# pulsewidth2.net
KiCad netlist of a schematic drawn in Altium Designer
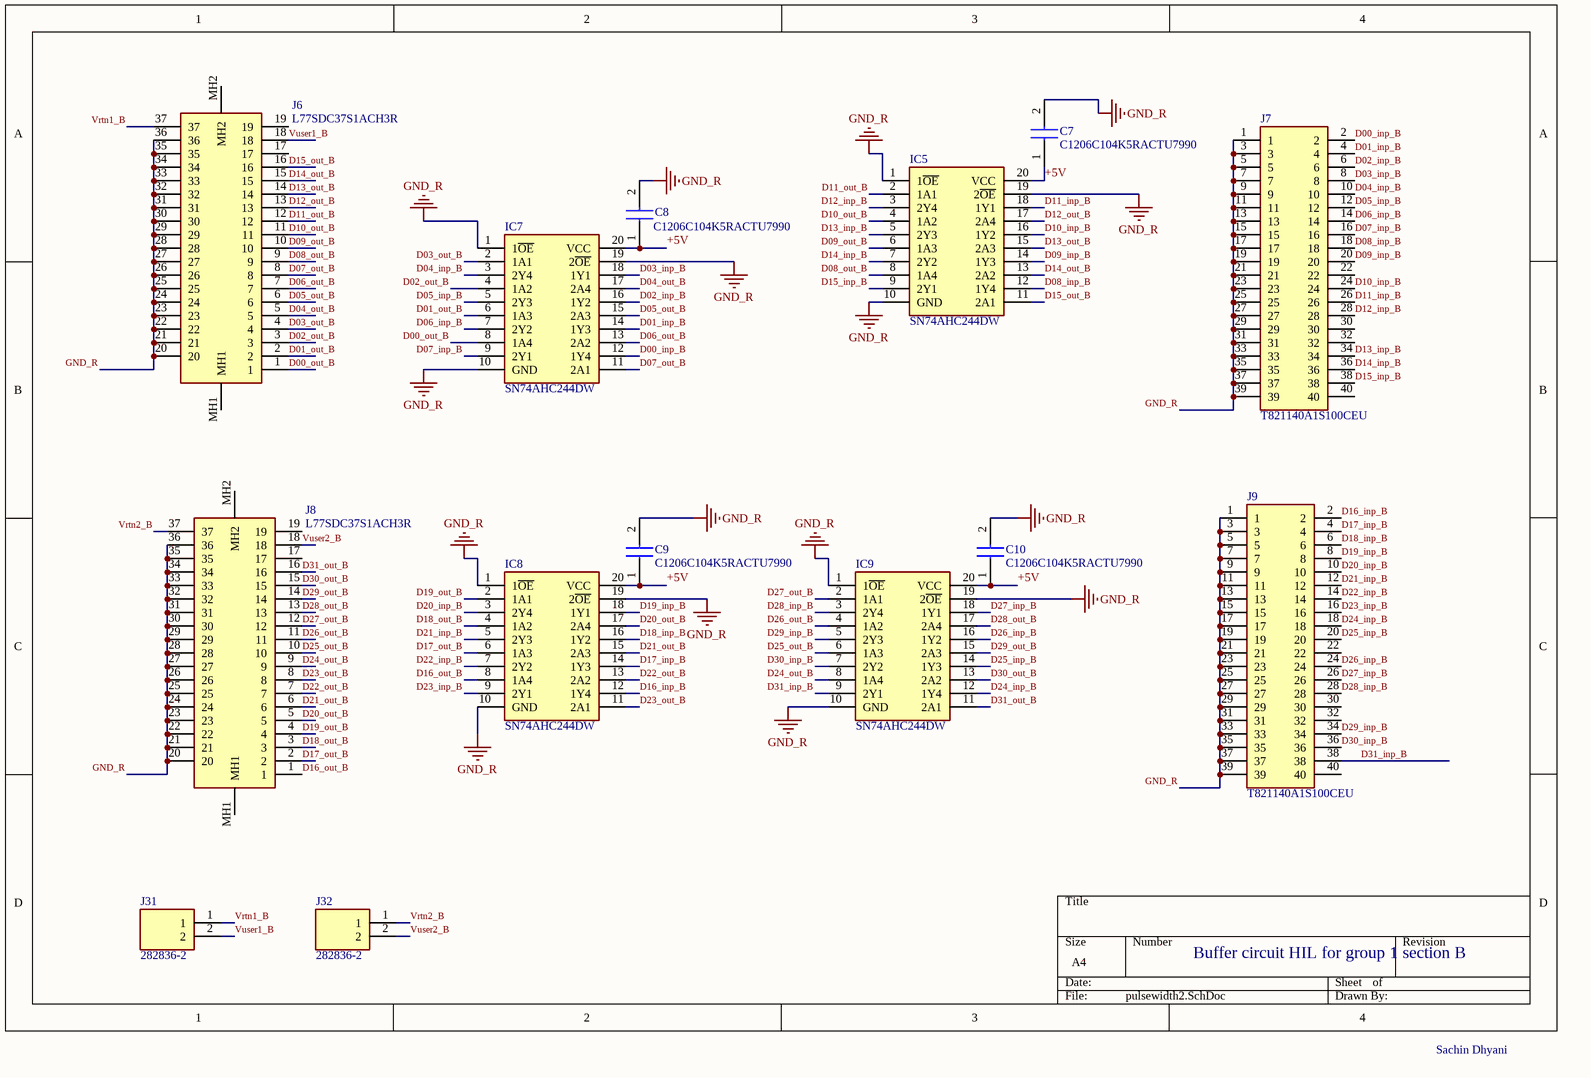
[diagram p0: pulsewidth2.SchDoc]

(export (version "E")
  (design (tool "Eeschema 10.0.6"))
  (components
    (comp (ref "C7")
      (value "C1206C104K5RACTU7990")
      (footprint "SamacSys:CAPC3216X88N")
      (description "Capacitor")
      (libsource (lib "*") (part "C1206C104K5RACTU7990"))
    )
    (comp (ref "C8")
      (value "C1206C104K5RACTU7990")
      (footprint "SamacSys:CAPC3216X88N")
      (description "Capacitor")
      (libsource (lib "*") (part "C1206C104K5RACTU7990"))
    )
    (comp (ref "C9")
      (value "C1206C104K5RACTU7990")
      (footprint "SamacSys:CAPC3216X88N")
      (description "Capacitor")
      (libsource (lib "*") (part "C1206C104K5RACTU7990"))
    )
    (comp (ref "C10")
      (value "C1206C104K5RACTU7990")
      (footprint "SamacSys:CAPC3216X88N")
      (description "Capacitor")
      (libsource (lib "*") (part "C1206C104K5RACTU7990"))
    )
    (comp (ref "IC5")
      (value "SN74AHC244DW")
      (footprint "SamacSys:SOIC127P1030X265-20N")
      (description "Integrated Circuit")
      (fields (field (name "MOUSER PART NUMBER") "595-SN74AHC244DW"))
      (libsource (lib "*") (part "SN74AHC244DW"))
    )
    (comp (ref "IC7")
      (value "SN74AHC244DW")
      (footprint "SamacSys:SOIC127P1030X265-20N")
      (description "Integrated Circuit")
      (fields (field (name "MOUSER PART NUMBER") "595-SN74AHC244DW"))
      (libsource (lib "*") (part "SN74AHC244DW"))
    )
    (comp (ref "IC8")
      (value "SN74AHC244DW")
      (footprint "SamacSys:SOIC127P1030X265-20N")
      (description "Integrated Circuit")
      (fields (field (name "MOUSER PART NUMBER") "595-SN74AHC244DW"))
      (libsource (lib "*") (part "SN74AHC244DW"))
    )
    (comp (ref "IC9")
      (value "SN74AHC244DW")
      (footprint "SamacSys:SOIC127P1030X265-20N")
      (description "Integrated Circuit")
      (fields (field (name "MOUSER PART NUMBER") "595-SN74AHC244DW"))
      (libsource (lib "*") (part "SN74AHC244DW"))
    )
    (comp (ref "J6")
      (value "L77SDC37S1ACH3R")
      (footprint "L77SDC37S1ACH3R")
      (description "Connector")
      (fields (field (name "MOUSER PART NUMBER") "523-L77SDC37S1ACH3R"))
      (libsource (lib "opel_Rt_comps") (part "L77SDC37S1ACH3R"))
    )
    (comp (ref "J7")
      (value "T821140A1S100CEU")
      (footprint "SamacSys:SHDR40W64P254X254_2X20_5842X895X915P")
      (description "Connector")
      (libsource (lib "*") (part "T821140A1S100CEU"))
    )
    (comp (ref "J8")
      (value "L77SDC37S1ACH3R")
      (footprint "L77SDC37S1ACH3R")
      (description "Connector")
      (fields (field (name "MOUSER PART NUMBER") "523-L77SDC37S1ACH3R"))
      (libsource (lib "opel_Rt_comps") (part "L77SDC37S1ACH3R"))
    )
    (comp (ref "J9")
      (value "T821140A1S100CEU")
      (footprint "SamacSys:SHDR40W64P254X254_2X20_5842X895X915P")
      (description "Connector")
      (libsource (lib "*") (part "T821140A1S100CEU"))
    )
    (comp (ref "J31")
      (value "282836-2")
      (footprint "SamacSys:2828362")
      (description "Connector")
      (fields (field (name "MOUSER PART NUMBER") "571-2828362"))
      (libsource (lib "*") (part "282836-2"))
    )
    (comp (ref "J32")
      (value "282836-2")
      (footprint "SamacSys:2828362")
      (description "Connector")
      (fields (field (name "MOUSER PART NUMBER") "571-2828362"))
      (libsource (lib "*") (part "282836-2"))
    )
  )
  (nets
    (net (code "1") (name "/+5V") (class "Default")
      (node (ref "C10") (pin "1") (pinfunction "1_1") (pintype "passive"))
      (node (ref "C7") (pin "1") (pinfunction "1_1") (pintype "passive"))
      (node (ref "C8") (pin "1") (pinfunction "1_1") (pintype "passive"))
      (node (ref "C9") (pin "1") (pinfunction "1_1") (pintype "passive"))
      (node (ref "IC5") (pin "20") (pinfunction "VCC_20") (pintype "passive"))
      (node (ref "IC7") (pin "20") (pinfunction "VCC_20") (pintype "passive"))
      (node (ref "IC8") (pin "20") (pinfunction "VCC_20") (pintype "passive"))
      (node (ref "IC9") (pin "20") (pinfunction "VCC_20") (pintype "passive"))
    )
    (net (code "2") (name "/D00_inp_B") (class "Default")
      (node (ref "IC7") (pin "12") (pinfunction "1Y4_12") (pintype "passive"))
      (node (ref "J7") (pin "2") (pinfunction "2_2") (pintype "passive"))
    )
    (net (code "3") (name "/D00_out_B") (class "Default")
      (node (ref "IC7") (pin "8") (pinfunction "1A4_8") (pintype "passive"))
      (node (ref "J6") (pin "1") (pinfunction "1_1") (pintype "passive"))
    )
    (net (code "4") (name "/D01_inp_B") (class "Default")
      (node (ref "IC7") (pin "14") (pinfunction "1Y3_14") (pintype "passive"))
      (node (ref "J7") (pin "4") (pinfunction "4_4") (pintype "passive"))
    )
    (net (code "5") (name "/D01_out_B") (class "Default")
      (node (ref "IC7") (pin "6") (pinfunction "1A3_6") (pintype "passive"))
      (node (ref "J6") (pin "2") (pinfunction "2_2") (pintype "passive"))
    )
    (net (code "6") (name "/D02_inp_B") (class "Default")
      (node (ref "IC7") (pin "16") (pinfunction "1Y2_16") (pintype "passive"))
      (node (ref "J7") (pin "6") (pinfunction "6_6") (pintype "passive"))
    )
    (net (code "7") (name "/D02_out_B") (class "Default")
      (node (ref "IC7") (pin "4") (pinfunction "1A2_4") (pintype "passive"))
      (node (ref "J6") (pin "3") (pinfunction "3_3") (pintype "passive"))
    )
    (net (code "8") (name "/D03_inp_B") (class "Default")
      (node (ref "IC7") (pin "18") (pinfunction "1Y1_18") (pintype "passive"))
      (node (ref "J7") (pin "8") (pinfunction "8_8") (pintype "passive"))
    )
    (net (code "9") (name "/D03_out_B") (class "Default")
      (node (ref "IC7") (pin "2") (pinfunction "1A1_2") (pintype "passive"))
      (node (ref "J6") (pin "4") (pinfunction "4_4") (pintype "passive"))
    )
    (net (code "10") (name "/D04_inp_B") (class "Default")
      (node (ref "IC7") (pin "3") (pinfunction "2Y4_3") (pintype "passive"))
      (node (ref "J7") (pin "10") (pinfunction "10_10") (pintype "passive"))
    )
    (net (code "11") (name "/D04_out_B") (class "Default")
      (node (ref "IC7") (pin "17") (pinfunction "2A4_17") (pintype "passive"))
      (node (ref "J6") (pin "5") (pinfunction "5_5") (pintype "passive"))
    )
    (net (code "12") (name "/D05_inp_B") (class "Default")
      (node (ref "IC7") (pin "5") (pinfunction "2Y3_5") (pintype "passive"))
      (node (ref "J7") (pin "12") (pinfunction "12_12") (pintype "passive"))
    )
    (net (code "13") (name "/D05_out_B") (class "Default")
      (node (ref "IC7") (pin "15") (pinfunction "2A3_15") (pintype "passive"))
      (node (ref "J6") (pin "6") (pinfunction "6_6") (pintype "passive"))
    )
    (net (code "14") (name "/D06_inp_B") (class "Default")
      (node (ref "IC7") (pin "7") (pinfunction "2Y2_7") (pintype "passive"))
      (node (ref "J7") (pin "14") (pinfunction "14_14") (pintype "passive"))
    )
    (net (code "15") (name "/D06_out_B") (class "Default")
      (node (ref "IC7") (pin "13") (pinfunction "2A2_13") (pintype "passive"))
      (node (ref "J6") (pin "7") (pinfunction "7_7") (pintype "passive"))
    )
    (net (code "16") (name "/D07_inp_B") (class "Default")
      (node (ref "IC7") (pin "9") (pinfunction "2Y1_9") (pintype "passive"))
      (node (ref "J7") (pin "16") (pinfunction "16_16") (pintype "passive"))
    )
    (net (code "17") (name "/D07_out_B") (class "Default")
      (node (ref "IC7") (pin "11") (pinfunction "2A1_11") (pintype "passive"))
      (node (ref "J6") (pin "8") (pinfunction "8_8") (pintype "passive"))
    )
    (net (code "18") (name "/D08_inp_B") (class "Default")
      (node (ref "IC5") (pin "12") (pinfunction "1Y4_12") (pintype "passive"))
      (node (ref "J7") (pin "18") (pinfunction "18_18") (pintype "passive"))
    )
    (net (code "19") (name "/D08_out_B") (class "Default")
      (node (ref "IC5") (pin "8") (pinfunction "1A4_8") (pintype "passive"))
      (node (ref "J6") (pin "9") (pinfunction "9_9") (pintype "passive"))
    )
    (net (code "20") (name "/D09_inp_B") (class "Default")
      (node (ref "IC5") (pin "14") (pinfunction "1Y3_14") (pintype "passive"))
      (node (ref "J7") (pin "20") (pinfunction "20_20") (pintype "passive"))
    )
    (net (code "21") (name "/D09_out_B") (class "Default")
      (node (ref "IC5") (pin "6") (pinfunction "1A3_6") (pintype "passive"))
      (node (ref "J6") (pin "10") (pinfunction "10_10") (pintype "passive"))
    )
    (net (code "22") (name "/D10_inp_B") (class "Default")
      (node (ref "IC5") (pin "16") (pinfunction "1Y2_16") (pintype "passive"))
      (node (ref "J7") (pin "24") (pinfunction "24_24") (pintype "passive"))
    )
    (net (code "23") (name "/D10_out_B") (class "Default")
      (node (ref "IC5") (pin "4") (pinfunction "1A2_4") (pintype "passive"))
      (node (ref "J6") (pin "11") (pinfunction "11_11") (pintype "passive"))
    )
    (net (code "24") (name "/D11_inp_B") (class "Default")
      (node (ref "IC5") (pin "18") (pinfunction "1Y1_18") (pintype "passive"))
      (node (ref "J7") (pin "26") (pinfunction "26_26") (pintype "passive"))
    )
    (net (code "25") (name "/D11_out_B") (class "Default")
      (node (ref "IC5") (pin "2") (pinfunction "1A1_2") (pintype "passive"))
      (node (ref "J6") (pin "12") (pinfunction "12_12") (pintype "passive"))
    )
    (net (code "26") (name "/D12_inp_B") (class "Default")
      (node (ref "IC5") (pin "3") (pinfunction "2Y4_3") (pintype "passive"))
      (node (ref "J7") (pin "28") (pinfunction "28_28") (pintype "passive"))
    )
    (net (code "27") (name "/D12_out_B") (class "Default")
      (node (ref "IC5") (pin "17") (pinfunction "2A4_17") (pintype "passive"))
      (node (ref "J6") (pin "13") (pinfunction "13_13") (pintype "passive"))
    )
    (net (code "28") (name "/D13_inp_B") (class "Default")
      (node (ref "IC5") (pin "5") (pinfunction "2Y3_5") (pintype "passive"))
      (node (ref "J7") (pin "34") (pinfunction "34_34") (pintype "passive"))
    )
    (net (code "29") (name "/D13_out_B") (class "Default")
      (node (ref "IC5") (pin "15") (pinfunction "2A3_15") (pintype "passive"))
      (node (ref "J6") (pin "14") (pinfunction "14_14") (pintype "passive"))
    )
    (net (code "30") (name "/D14_inp_B") (class "Default")
      (node (ref "IC5") (pin "7") (pinfunction "2Y2_7") (pintype "passive"))
      (node (ref "J7") (pin "36") (pinfunction "36_36") (pintype "passive"))
    )
    (net (code "31") (name "/D14_out_B") (class "Default")
      (node (ref "IC5") (pin "13") (pinfunction "2A2_13") (pintype "passive"))
      (node (ref "J6") (pin "15") (pinfunction "15_15") (pintype "passive"))
    )
    (net (code "32") (name "/D15_inp_B") (class "Default")
      (node (ref "IC5") (pin "9") (pinfunction "2Y1_9") (pintype "passive"))
      (node (ref "J7") (pin "38") (pinfunction "38_38") (pintype "passive"))
    )
    (net (code "33") (name "/D15_out_B") (class "Default")
      (node (ref "IC5") (pin "11") (pinfunction "2A1_11") (pintype "passive"))
      (node (ref "J6") (pin "16") (pinfunction "16_16") (pintype "passive"))
    )
    (net (code "34") (name "/D16_inp_B") (class "Default")
      (node (ref "IC8") (pin "12") (pinfunction "1Y4_12") (pintype "passive"))
      (node (ref "J9") (pin "2") (pinfunction "2_2") (pintype "passive"))
    )
    (net (code "35") (name "/D16_out_B") (class "Default")
      (node (ref "IC8") (pin "8") (pinfunction "1A4_8") (pintype "passive"))
      (node (ref "J8") (pin "1") (pinfunction "1_1") (pintype "passive"))
    )
    (net (code "36") (name "/D17_inp_B") (class "Default")
      (node (ref "IC8") (pin "14") (pinfunction "1Y3_14") (pintype "passive"))
      (node (ref "J9") (pin "4") (pinfunction "4_4") (pintype "passive"))
    )
    (net (code "37") (name "/D17_out_B") (class "Default")
      (node (ref "IC8") (pin "6") (pinfunction "1A3_6") (pintype "passive"))
      (node (ref "J8") (pin "2") (pinfunction "2_2") (pintype "passive"))
    )
    (net (code "38") (name "/D18_inp_B") (class "Default")
      (node (ref "IC8") (pin "16") (pinfunction "1Y2_16") (pintype "passive"))
      (node (ref "J9") (pin "6") (pinfunction "6_6") (pintype "passive"))
    )
    (net (code "39") (name "/D18_out_B") (class "Default")
      (node (ref "IC8") (pin "4") (pinfunction "1A2_4") (pintype "passive"))
      (node (ref "J8") (pin "3") (pinfunction "3_3") (pintype "passive"))
    )
    (net (code "40") (name "/D19_inp_B") (class "Default")
      (node (ref "IC8") (pin "18") (pinfunction "1Y1_18") (pintype "passive"))
      (node (ref "J9") (pin "8") (pinfunction "8_8") (pintype "passive"))
    )
    (net (code "41") (name "/D19_out_B") (class "Default")
      (node (ref "IC8") (pin "2") (pinfunction "1A1_2") (pintype "passive"))
      (node (ref "J8") (pin "4") (pinfunction "4_4") (pintype "passive"))
    )
    (net (code "42") (name "/D20_inp_B") (class "Default")
      (node (ref "IC8") (pin "3") (pinfunction "2Y4_3") (pintype "passive"))
      (node (ref "J9") (pin "10") (pinfunction "10_10") (pintype "passive"))
    )
    (net (code "43") (name "/D20_out_B") (class "Default")
      (node (ref "IC8") (pin "17") (pinfunction "2A4_17") (pintype "passive"))
      (node (ref "J8") (pin "5") (pinfunction "5_5") (pintype "passive"))
    )
    (net (code "44") (name "/D21_inp_B") (class "Default")
      (node (ref "IC8") (pin "5") (pinfunction "2Y3_5") (pintype "passive"))
      (node (ref "J9") (pin "12") (pinfunction "12_12") (pintype "passive"))
    )
    (net (code "45") (name "/D21_out_B") (class "Default")
      (node (ref "IC8") (pin "15") (pinfunction "2A3_15") (pintype "passive"))
      (node (ref "J8") (pin "6") (pinfunction "6_6") (pintype "passive"))
    )
    (net (code "46") (name "/D22_inp_B") (class "Default")
      (node (ref "IC8") (pin "7") (pinfunction "2Y2_7") (pintype "passive"))
      (node (ref "J9") (pin "14") (pinfunction "14_14") (pintype "passive"))
    )
    (net (code "47") (name "/D22_out_B") (class "Default")
      (node (ref "IC8") (pin "13") (pinfunction "2A2_13") (pintype "passive"))
      (node (ref "J8") (pin "7") (pinfunction "7_7") (pintype "passive"))
    )
    (net (code "48") (name "/D23_inp_B") (class "Default")
      (node (ref "IC8") (pin "9") (pinfunction "2Y1_9") (pintype "passive"))
      (node (ref "J9") (pin "16") (pinfunction "16_16") (pintype "passive"))
    )
    (net (code "49") (name "/D23_out_B") (class "Default")
      (node (ref "IC8") (pin "11") (pinfunction "2A1_11") (pintype "passive"))
      (node (ref "J8") (pin "8") (pinfunction "8_8") (pintype "passive"))
    )
    (net (code "50") (name "/D24_inp_B") (class "Default")
      (node (ref "IC9") (pin "12") (pinfunction "1Y4_12") (pintype "passive"))
      (node (ref "J9") (pin "18") (pinfunction "18_18") (pintype "passive"))
    )
    (net (code "51") (name "/D24_out_B") (class "Default")
      (node (ref "IC9") (pin "8") (pinfunction "1A4_8") (pintype "passive"))
      (node (ref "J8") (pin "9") (pinfunction "9_9") (pintype "passive"))
    )
    (net (code "52") (name "/D25_inp_B") (class "Default")
      (node (ref "IC9") (pin "14") (pinfunction "1Y3_14") (pintype "passive"))
      (node (ref "J9") (pin "20") (pinfunction "20_20") (pintype "passive"))
    )
    (net (code "53") (name "/D25_out_B") (class "Default")
      (node (ref "IC9") (pin "6") (pinfunction "1A3_6") (pintype "passive"))
      (node (ref "J8") (pin "10") (pinfunction "10_10") (pintype "passive"))
    )
    (net (code "54") (name "/D26_inp_B") (class "Default")
      (node (ref "IC9") (pin "16") (pinfunction "1Y2_16") (pintype "passive"))
      (node (ref "J9") (pin "24") (pinfunction "24_24") (pintype "passive"))
    )
    (net (code "55") (name "/D26_out_B") (class "Default")
      (node (ref "IC9") (pin "4") (pinfunction "1A2_4") (pintype "passive"))
      (node (ref "J8") (pin "11") (pinfunction "11_11") (pintype "passive"))
    )
    (net (code "56") (name "/D27_inp_B") (class "Default")
      (node (ref "IC9") (pin "18") (pinfunction "1Y1_18") (pintype "passive"))
      (node (ref "J9") (pin "26") (pinfunction "26_26") (pintype "passive"))
    )
    (net (code "57") (name "/D27_out_B") (class "Default")
      (node (ref "IC9") (pin "2") (pinfunction "1A1_2") (pintype "passive"))
      (node (ref "J8") (pin "12") (pinfunction "12_12") (pintype "passive"))
    )
    (net (code "58") (name "/D28_inp_B") (class "Default")
      (node (ref "IC9") (pin "3") (pinfunction "2Y4_3") (pintype "passive"))
      (node (ref "J9") (pin "28") (pinfunction "28_28") (pintype "passive"))
    )
    (net (code "59") (name "/D28_out_B") (class "Default")
      (node (ref "IC9") (pin "17") (pinfunction "2A4_17") (pintype "passive"))
      (node (ref "J8") (pin "13") (pinfunction "13_13") (pintype "passive"))
    )
    (net (code "60") (name "/D29_inp_B") (class "Default")
      (node (ref "IC9") (pin "5") (pinfunction "2Y3_5") (pintype "passive"))
      (node (ref "J9") (pin "34") (pinfunction "34_34") (pintype "passive"))
    )
    (net (code "61") (name "/D29_out_B") (class "Default")
      (node (ref "IC9") (pin "15") (pinfunction "2A3_15") (pintype "passive"))
      (node (ref "J8") (pin "14") (pinfunction "14_14") (pintype "passive"))
    )
    (net (code "62") (name "/D30_inp_B") (class "Default")
      (node (ref "IC9") (pin "7") (pinfunction "2Y2_7") (pintype "passive"))
      (node (ref "J9") (pin "36") (pinfunction "36_36") (pintype "passive"))
    )
    (net (code "63") (name "/D30_out_B") (class "Default")
      (node (ref "IC9") (pin "13") (pinfunction "2A2_13") (pintype "passive"))
      (node (ref "J8") (pin "15") (pinfunction "15_15") (pintype "passive"))
    )
    (net (code "64") (name "/D31_inp_B") (class "Default")
      (node (ref "IC9") (pin "9") (pinfunction "2Y1_9") (pintype "passive"))
      (node (ref "J9") (pin "38") (pinfunction "38_38") (pintype "passive"))
    )
    (net (code "65") (name "/D31_out_B") (class "Default")
      (node (ref "IC9") (pin "11") (pinfunction "2A1_11") (pintype "passive"))
      (node (ref "J8") (pin "16") (pinfunction "16_16") (pintype "passive"))
    )
    (net (code "66") (name "/Vrtn1_B") (class "Default")
      (node (ref "J31") (pin "1") (pinfunction "1_1") (pintype "passive"))
      (node (ref "J6") (pin "37") (pinfunction "37_37") (pintype "passive"))
    )
    (net (code "67") (name "/Vrtn2_B") (class "Default")
      (node (ref "J32") (pin "1") (pinfunction "1_1") (pintype "passive"))
      (node (ref "J8") (pin "37") (pinfunction "37_37") (pintype "passive"))
    )
    (net (code "68") (name "/Vuser1_B") (class "Default")
      (node (ref "J31") (pin "2") (pinfunction "2_2") (pintype "passive"))
      (node (ref "J6") (pin "18") (pinfunction "18_18") (pintype "passive"))
    )
    (net (code "69") (name "/Vuser2_B") (class "Default")
      (node (ref "J32") (pin "2") (pinfunction "2_2") (pintype "passive"))
      (node (ref "J8") (pin "18") (pinfunction "18_18") (pintype "passive"))
    )
    (net (code "70") (name "GND_R") (class "Default")
      (node (ref "C10") (pin "2") (pinfunction "2_2") (pintype "passive"))
      (node (ref "C7") (pin "2") (pinfunction "2_2") (pintype "passive"))
      (node (ref "C8") (pin "2") (pinfunction "2_2") (pintype "passive"))
      (node (ref "C9") (pin "2") (pinfunction "2_2") (pintype "passive"))
      (node (ref "IC5") (pin "1") (pinfunction "1~{OE}_1") (pintype "passive"))
      (node (ref "IC5") (pin "10") (pinfunction "GND_10") (pintype "passive"))
      (node (ref "IC5") (pin "19") (pinfunction "2~{OE}_19") (pintype "passive"))
      (node (ref "IC7") (pin "1") (pinfunction "1~{OE}_1") (pintype "passive"))
      (node (ref "IC7") (pin "10") (pinfunction "GND_10") (pintype "passive"))
      (node (ref "IC7") (pin "19") (pinfunction "2~{OE}_19") (pintype "passive"))
      (node (ref "IC8") (pin "1") (pinfunction "1~{OE}_1") (pintype "passive"))
      (node (ref "IC8") (pin "10") (pinfunction "GND_10") (pintype "passive"))
      (node (ref "IC8") (pin "19") (pinfunction "2~{OE}_19") (pintype "passive"))
      (node (ref "IC9") (pin "1") (pinfunction "1~{OE}_1") (pintype "passive"))
      (node (ref "IC9") (pin "10") (pinfunction "GND_10") (pintype "passive"))
      (node (ref "IC9") (pin "19") (pinfunction "2~{OE}_19") (pintype "passive"))
      (node (ref "J6") (pin "20") (pinfunction "20_20") (pintype "passive"))
      (node (ref "J6") (pin "21") (pinfunction "21_21") (pintype "passive"))
      (node (ref "J6") (pin "22") (pinfunction "22_22") (pintype "passive"))
      (node (ref "J6") (pin "23") (pinfunction "23_23") (pintype "passive"))
      (node (ref "J6") (pin "24") (pinfunction "24_24") (pintype "passive"))
      (node (ref "J6") (pin "25") (pinfunction "25_25") (pintype "passive"))
      (node (ref "J6") (pin "26") (pinfunction "26_26") (pintype "passive"))
      (node (ref "J6") (pin "27") (pinfunction "27_27") (pintype "passive"))
      (node (ref "J6") (pin "28") (pinfunction "28_28") (pintype "passive"))
      (node (ref "J6") (pin "29") (pinfunction "29_29") (pintype "passive"))
      (node (ref "J6") (pin "30") (pinfunction "30_30") (pintype "passive"))
      (node (ref "J6") (pin "31") (pinfunction "31_31") (pintype "passive"))
      (node (ref "J6") (pin "32") (pinfunction "32_32") (pintype "passive"))
      (node (ref "J6") (pin "33") (pinfunction "33_33") (pintype "passive"))
      (node (ref "J6") (pin "34") (pinfunction "34_34") (pintype "passive"))
      (node (ref "J6") (pin "35") (pinfunction "35_35") (pintype "passive"))
      (node (ref "J6") (pin "36") (pinfunction "36_36") (pintype "passive"))
      (node (ref "J7") (pin "1") (pinfunction "1_1") (pintype "passive"))
      (node (ref "J7") (pin "11") (pinfunction "11_11") (pintype "passive"))
      (node (ref "J7") (pin "13") (pinfunction "13_13") (pintype "passive"))
      (node (ref "J7") (pin "15") (pinfunction "15_15") (pintype "passive"))
      (node (ref "J7") (pin "17") (pinfunction "17_17") (pintype "passive"))
      (node (ref "J7") (pin "19") (pinfunction "19_19") (pintype "passive"))
      (node (ref "J7") (pin "21") (pinfunction "21_21") (pintype "passive"))
      (node (ref "J7") (pin "23") (pinfunction "23_23") (pintype "passive"))
      (node (ref "J7") (pin "25") (pinfunction "25_25") (pintype "passive"))
      (node (ref "J7") (pin "27") (pinfunction "27_27") (pintype "passive"))
      (node (ref "J7") (pin "29") (pinfunction "29_29") (pintype "passive"))
      (node (ref "J7") (pin "3") (pinfunction "3_3") (pintype "passive"))
      (node (ref "J7") (pin "31") (pinfunction "31_31") (pintype "passive"))
      (node (ref "J7") (pin "33") (pinfunction "33_33") (pintype "passive"))
      (node (ref "J7") (pin "35") (pinfunction "35_35") (pintype "passive"))
      (node (ref "J7") (pin "37") (pinfunction "37_37") (pintype "passive"))
      (node (ref "J7") (pin "39") (pinfunction "39_39") (pintype "passive"))
      (node (ref "J7") (pin "5") (pinfunction "5_5") (pintype "passive"))
      (node (ref "J7") (pin "7") (pinfunction "7_7") (pintype "passive"))
      (node (ref "J7") (pin "9") (pinfunction "9_9") (pintype "passive"))
      (node (ref "J8") (pin "20") (pinfunction "20_20") (pintype "passive"))
      (node (ref "J8") (pin "21") (pinfunction "21_21") (pintype "passive"))
      (node (ref "J8") (pin "22") (pinfunction "22_22") (pintype "passive"))
      (node (ref "J8") (pin "23") (pinfunction "23_23") (pintype "passive"))
      (node (ref "J8") (pin "24") (pinfunction "24_24") (pintype "passive"))
      (node (ref "J8") (pin "25") (pinfunction "25_25") (pintype "passive"))
      (node (ref "J8") (pin "26") (pinfunction "26_26") (pintype "passive"))
      (node (ref "J8") (pin "27") (pinfunction "27_27") (pintype "passive"))
      (node (ref "J8") (pin "28") (pinfunction "28_28") (pintype "passive"))
      (node (ref "J8") (pin "29") (pinfunction "29_29") (pintype "passive"))
      (node (ref "J8") (pin "30") (pinfunction "30_30") (pintype "passive"))
      (node (ref "J8") (pin "31") (pinfunction "31_31") (pintype "passive"))
      (node (ref "J8") (pin "32") (pinfunction "32_32") (pintype "passive"))
      (node (ref "J8") (pin "33") (pinfunction "33_33") (pintype "passive"))
      (node (ref "J8") (pin "34") (pinfunction "34_34") (pintype "passive"))
      (node (ref "J8") (pin "35") (pinfunction "35_35") (pintype "passive"))
      (node (ref "J8") (pin "36") (pinfunction "36_36") (pintype "passive"))
      (node (ref "J9") (pin "1") (pinfunction "1_1") (pintype "passive"))
      (node (ref "J9") (pin "11") (pinfunction "11_11") (pintype "passive"))
      (node (ref "J9") (pin "13") (pinfunction "13_13") (pintype "passive"))
      (node (ref "J9") (pin "15") (pinfunction "15_15") (pintype "passive"))
      (node (ref "J9") (pin "17") (pinfunction "17_17") (pintype "passive"))
      (node (ref "J9") (pin "19") (pinfunction "19_19") (pintype "passive"))
      (node (ref "J9") (pin "21") (pinfunction "21_21") (pintype "passive"))
      (node (ref "J9") (pin "23") (pinfunction "23_23") (pintype "passive"))
      (node (ref "J9") (pin "25") (pinfunction "25_25") (pintype "passive"))
      (node (ref "J9") (pin "27") (pinfunction "27_27") (pintype "passive"))
      (node (ref "J9") (pin "29") (pinfunction "29_29") (pintype "passive"))
      (node (ref "J9") (pin "3") (pinfunction "3_3") (pintype "passive"))
      (node (ref "J9") (pin "31") (pinfunction "31_31") (pintype "passive"))
      (node (ref "J9") (pin "33") (pinfunction "33_33") (pintype "passive"))
      (node (ref "J9") (pin "35") (pinfunction "35_35") (pintype "passive"))
      (node (ref "J9") (pin "37") (pinfunction "37_37") (pintype "passive"))
      (node (ref "J9") (pin "39") (pinfunction "39_39") (pintype "passive"))
      (node (ref "J9") (pin "5") (pinfunction "5_5") (pintype "passive"))
      (node (ref "J9") (pin "7") (pinfunction "7_7") (pintype "passive"))
      (node (ref "J9") (pin "9") (pinfunction "9_9") (pintype "passive"))
    )
    (net (code "71") (name "unconnected-(J6-Pad17)") (class "Default")
      (node (ref "J6") (pin "17") (pinfunction "17_17") (pintype "passive"))
    )
    (net (code "72") (name "unconnected-(J6-Pad19)") (class "Default")
      (node (ref "J6") (pin "19") (pinfunction "19_19") (pintype "passive"))
    )
    (net (code "73") (name "unconnected-(J6-PadMH1)") (class "Default")
      (node (ref "J6") (pin "MH1") (pinfunction "MH1_MH1") (pintype "passive"))
    )
    (net (code "74") (name "unconnected-(J6-PadMH2)") (class "Default")
      (node (ref "J6") (pin "MH2") (pinfunction "MH2_MH2") (pintype "passive"))
    )
    (net (code "75") (name "unconnected-(J7-Pad22)") (class "Default")
      (node (ref "J7") (pin "22") (pinfunction "22_22") (pintype "passive"))
    )
    (net (code "76") (name "unconnected-(J7-Pad30)") (class "Default")
      (node (ref "J7") (pin "30") (pinfunction "30_30") (pintype "passive"))
    )
    (net (code "77") (name "unconnected-(J7-Pad32)") (class "Default")
      (node (ref "J7") (pin "32") (pinfunction "32_32") (pintype "passive"))
    )
    (net (code "78") (name "unconnected-(J7-Pad40)") (class "Default")
      (node (ref "J7") (pin "40") (pinfunction "40_40") (pintype "passive"))
    )
    (net (code "79") (name "unconnected-(J8-Pad17)") (class "Default")
      (node (ref "J8") (pin "17") (pinfunction "17_17") (pintype "passive"))
    )
    (net (code "80") (name "unconnected-(J8-Pad19)") (class "Default")
      (node (ref "J8") (pin "19") (pinfunction "19_19") (pintype "passive"))
    )
    (net (code "81") (name "unconnected-(J8-PadMH1)") (class "Default")
      (node (ref "J8") (pin "MH1") (pinfunction "MH1_MH1") (pintype "passive"))
    )
    (net (code "82") (name "unconnected-(J8-PadMH2)") (class "Default")
      (node (ref "J8") (pin "MH2") (pinfunction "MH2_MH2") (pintype "passive"))
    )
    (net (code "83") (name "unconnected-(J9-Pad22)") (class "Default")
      (node (ref "J9") (pin "22") (pinfunction "22_22") (pintype "passive"))
    )
    (net (code "84") (name "unconnected-(J9-Pad30)") (class "Default")
      (node (ref "J9") (pin "30") (pinfunction "30_30") (pintype "passive"))
    )
    (net (code "85") (name "unconnected-(J9-Pad32)") (class "Default")
      (node (ref "J9") (pin "32") (pinfunction "32_32") (pintype "passive"))
    )
    (net (code "86") (name "unconnected-(J9-Pad40)") (class "Default")
      (node (ref "J9") (pin "40") (pinfunction "40_40") (pintype "passive"))
    )
  )
)
